# CRSC0002.net
KiCad netlist of a schematic drawn in Altium Designer
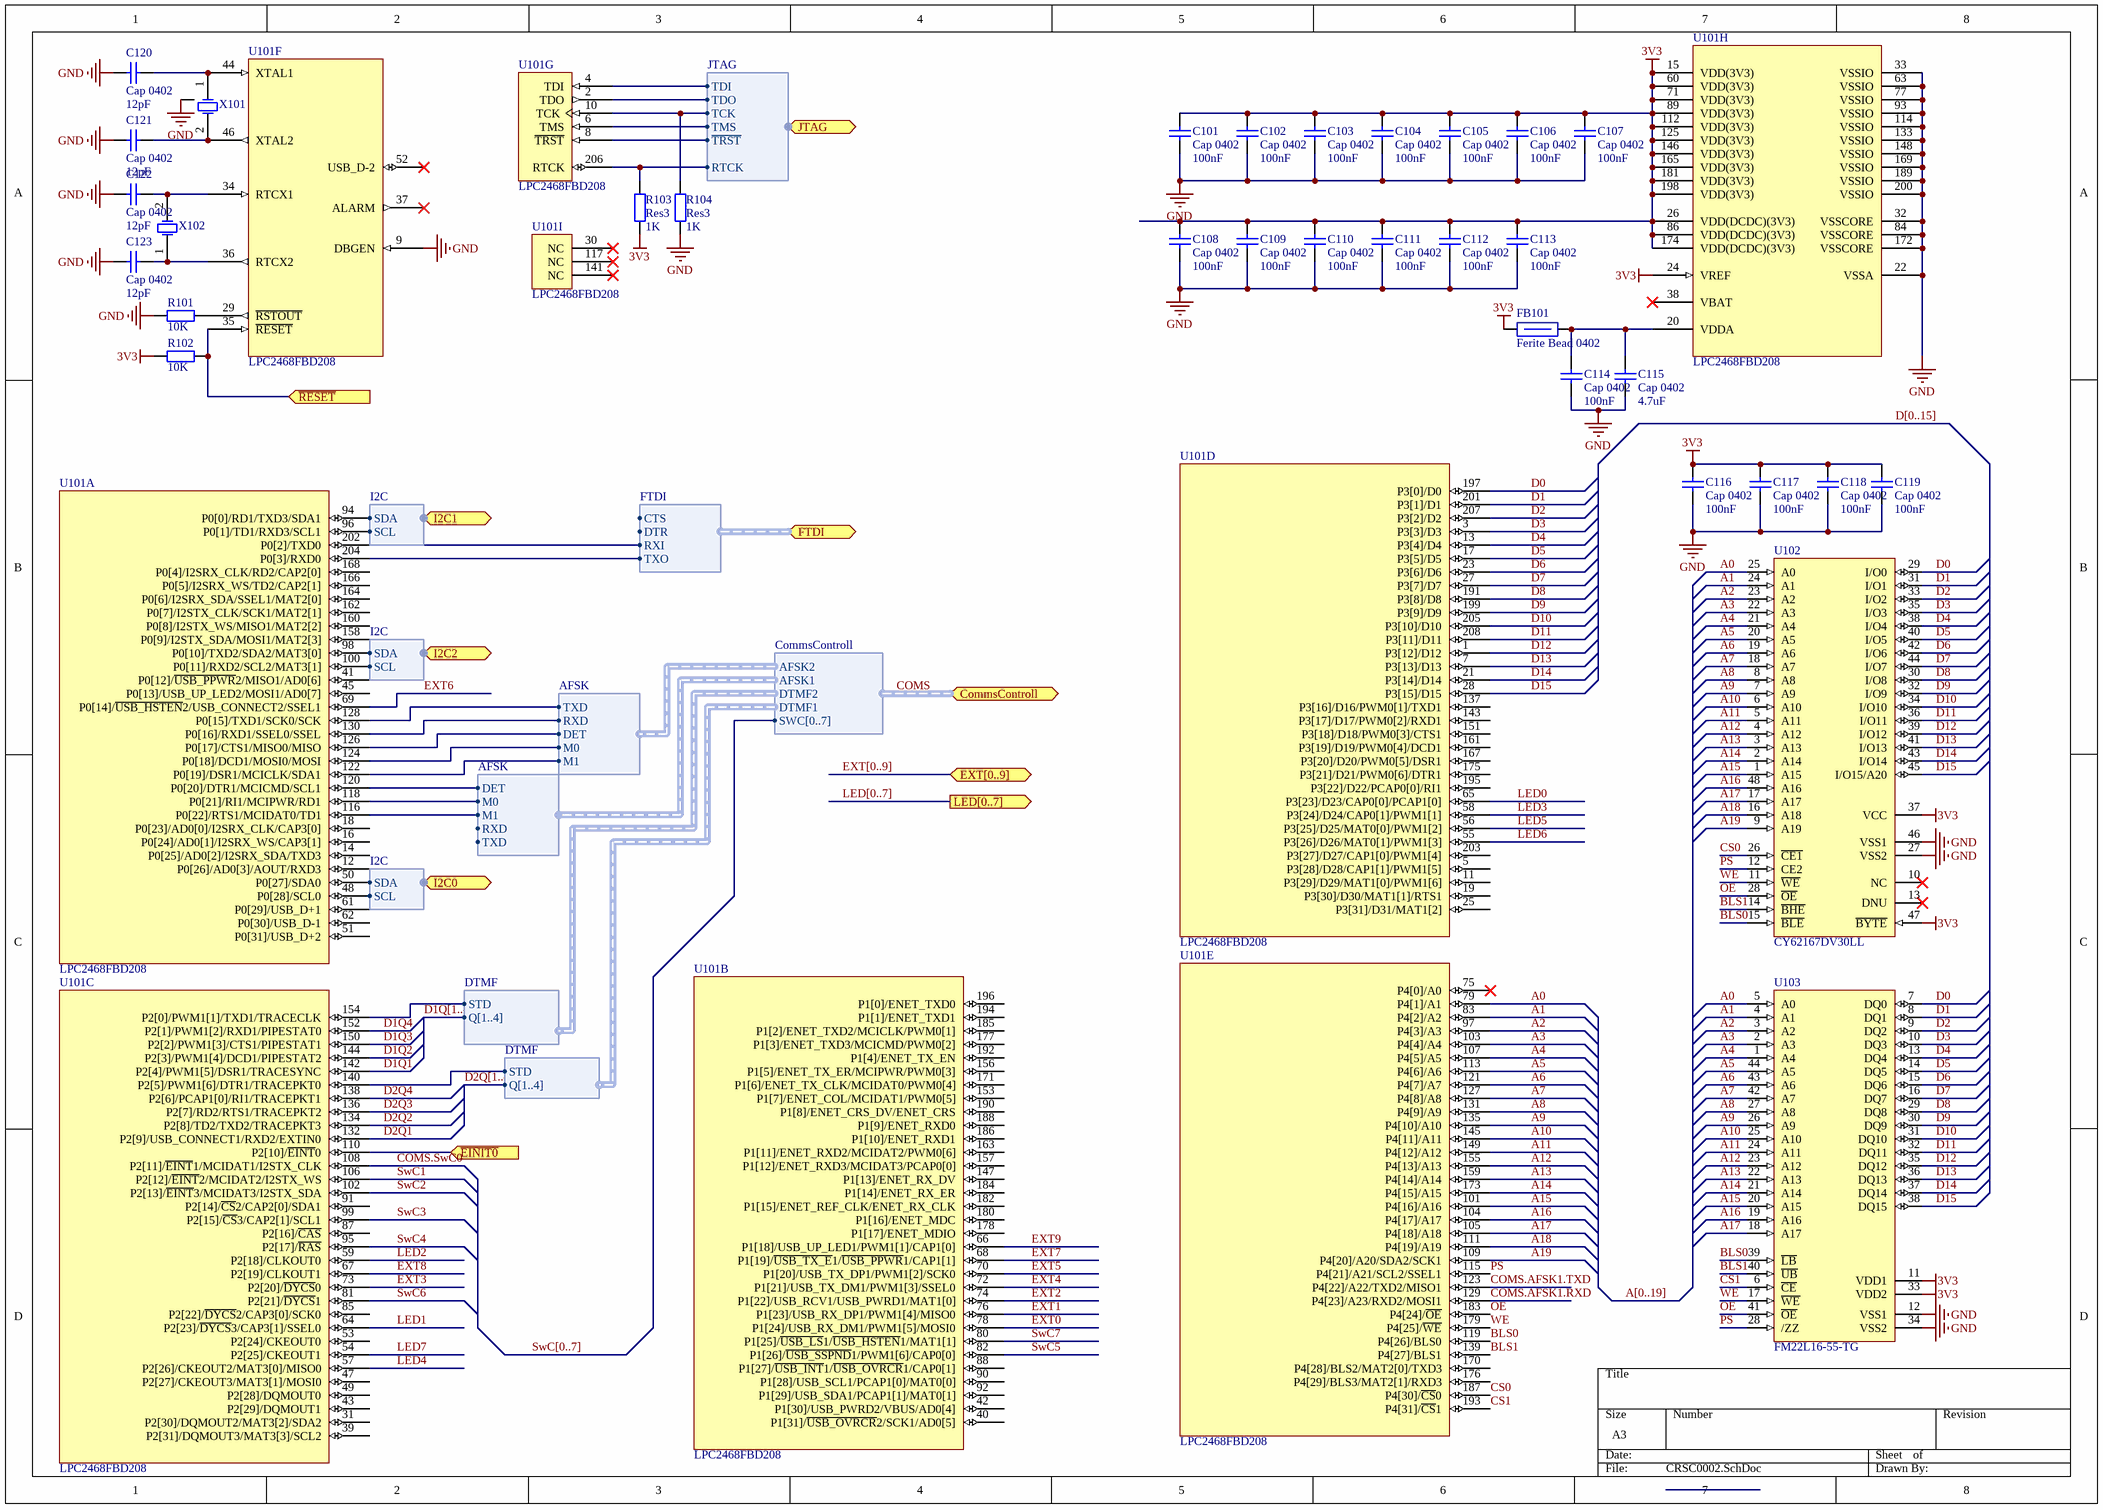
[diagram p0: CRSC0002.SchDoc]

(export (version "E")
  (design (tool "Eeschema 10.0.6"))
  (components
    (comp (ref "C101")
      (value "Cap 0402")
      (footprint "CAPC1005X06L")
      (description "Capacitor")
      (fields (field (name "ALTIUM_VALUE") "100nF") (field (name "PUBLISHER") "Altium Limited"))
      (libsource (lib "CSC") (part "Cap 0402"))
    )
    (comp (ref "C102")
      (value "Cap 0402")
      (footprint "CAPC1005X06L")
      (description "Capacitor")
      (fields (field (name "ALTIUM_VALUE") "100nF") (field (name "PUBLISHER") "Altium Limited"))
      (libsource (lib "CSC") (part "Cap 0402"))
    )
    (comp (ref "C103")
      (value "Cap 0402")
      (footprint "CAPC1005X06L")
      (description "Capacitor")
      (fields (field (name "ALTIUM_VALUE") "100nF") (field (name "PUBLISHER") "Altium Limited"))
      (libsource (lib "CSC") (part "Cap 0402"))
    )
    (comp (ref "C104")
      (value "Cap 0402")
      (footprint "CAPC1005X06L")
      (description "Capacitor")
      (fields (field (name "ALTIUM_VALUE") "100nF") (field (name "PUBLISHER") "Altium Limited"))
      (libsource (lib "CSC") (part "Cap 0402"))
    )
    (comp (ref "C105")
      (value "Cap 0402")
      (footprint "CAPC1005X06L")
      (description "Capacitor")
      (fields (field (name "ALTIUM_VALUE") "100nF") (field (name "PUBLISHER") "Altium Limited"))
      (libsource (lib "CSC") (part "Cap 0402"))
    )
    (comp (ref "C106")
      (value "Cap 0402")
      (footprint "CAPC1005X06L")
      (description "Capacitor")
      (fields (field (name "ALTIUM_VALUE") "100nF") (field (name "PUBLISHER") "Altium Limited"))
      (libsource (lib "CSC") (part "Cap 0402"))
    )
    (comp (ref "C107")
      (value "Cap 0402")
      (footprint "CAPC1005X06L")
      (description "Capacitor")
      (fields (field (name "ALTIUM_VALUE") "100nF") (field (name "PUBLISHER") "Altium Limited"))
      (libsource (lib "CSC") (part "Cap 0402"))
    )
    (comp (ref "C108")
      (value "Cap 0402")
      (footprint "CAPC1005X06L")
      (description "Capacitor")
      (fields (field (name "ALTIUM_VALUE") "100nF") (field (name "PUBLISHER") "Altium Limited"))
      (libsource (lib "CSC") (part "Cap 0402"))
    )
    (comp (ref "C109")
      (value "Cap 0402")
      (footprint "CAPC1005X06L")
      (description "Capacitor")
      (fields (field (name "ALTIUM_VALUE") "100nF") (field (name "PUBLISHER") "Altium Limited"))
      (libsource (lib "CSC") (part "Cap 0402"))
    )
    (comp (ref "C110")
      (value "Cap 0402")
      (footprint "CAPC1005X06L")
      (description "Capacitor")
      (fields (field (name "ALTIUM_VALUE") "100nF") (field (name "PUBLISHER") "Altium Limited"))
      (libsource (lib "CSC") (part "Cap 0402"))
    )
    (comp (ref "C111")
      (value "Cap 0402")
      (footprint "CAPC1005X06L")
      (description "Capacitor")
      (fields (field (name "ALTIUM_VALUE") "100nF") (field (name "PUBLISHER") "Altium Limited"))
      (libsource (lib "CSC") (part "Cap 0402"))
    )
    (comp (ref "C112")
      (value "Cap 0402")
      (footprint "CAPC1005X06L")
      (description "Capacitor")
      (fields (field (name "ALTIUM_VALUE") "100nF") (field (name "PUBLISHER") "Altium Limited"))
      (libsource (lib "CSC") (part "Cap 0402"))
    )
    (comp (ref "C113")
      (value "Cap 0402")
      (footprint "CAPC1005X06L")
      (description "Capacitor")
      (fields (field (name "ALTIUM_VALUE") "100nF") (field (name "PUBLISHER") "Altium Limited"))
      (libsource (lib "CSC") (part "Cap 0402"))
    )
    (comp (ref "C114")
      (value "Cap 0402")
      (footprint "CAPC1005X06L")
      (description "Capacitor")
      (fields (field (name "ALTIUM_VALUE") "100nF") (field (name "PUBLISHER") "Altium Limited"))
      (libsource (lib "CSC") (part "Cap 0402"))
    )
    (comp (ref "C115")
      (value "Cap 0402")
      (footprint "CAPC1005X06L")
      (description "Capacitor")
      (fields (field (name "ALTIUM_VALUE") "4.7uF") (field (name "PUBLISHER") "Altium Limited"))
      (libsource (lib "CSC") (part "Cap 0402"))
    )
    (comp (ref "C116")
      (value "Cap 0402")
      (footprint "CAPC1005X06L")
      (description "Capacitor")
      (fields (field (name "ALTIUM_VALUE") "100nF") (field (name "PUBLISHER") "Altium Limited"))
      (libsource (lib "CSC") (part "Cap 0402"))
    )
    (comp (ref "C117")
      (value "Cap 0402")
      (footprint "CAPC1005X06L")
      (description "Capacitor")
      (fields (field (name "ALTIUM_VALUE") "100nF") (field (name "PUBLISHER") "Altium Limited"))
      (libsource (lib "CSC") (part "Cap 0402"))
    )
    (comp (ref "C118")
      (value "Cap 0402")
      (footprint "CAPC1005X06L")
      (description "Capacitor")
      (fields (field (name "ALTIUM_VALUE") "100nF") (field (name "PUBLISHER") "Altium Limited"))
      (libsource (lib "CSC") (part "Cap 0402"))
    )
    (comp (ref "C119")
      (value "Cap 0402")
      (footprint "CAPC1005X06L")
      (description "Capacitor")
      (fields (field (name "ALTIUM_VALUE") "100nF") (field (name "PUBLISHER") "Altium Limited"))
      (libsource (lib "CSC") (part "Cap 0402"))
    )
    (comp (ref "C120")
      (value "Cap 0402")
      (footprint "CAPC1005X06L")
      (description "Capacitor")
      (fields (field (name "ALTIUM_VALUE") "12pF") (field (name "PUBLISHER") "Altium Limited"))
      (libsource (lib "CSC") (part "Cap 0402"))
    )
    (comp (ref "C121")
      (value "Cap 0402")
      (footprint "CAPC1005X06L")
      (description "Capacitor")
      (fields (field (name "ALTIUM_VALUE") "12pF") (field (name "PUBLISHER") "Altium Limited"))
      (libsource (lib "CSC") (part "Cap 0402"))
    )
    (comp (ref "C122")
      (value "Cap 0402")
      (footprint "CAPC1005X06L")
      (description "Capacitor")
      (fields (field (name "ALTIUM_VALUE") "12pF") (field (name "PUBLISHER") "Altium Limited"))
      (libsource (lib "CSC") (part "Cap 0402"))
    )
    (comp (ref "C123")
      (value "Cap 0402")
      (footprint "CAPC1005X06L")
      (description "Capacitor")
      (fields (field (name "ALTIUM_VALUE") "12pF") (field (name "PUBLISHER") "Altium Limited"))
      (libsource (lib "CSC") (part "Cap 0402"))
    )
    (comp (ref "FB101")
      (value "Ferite Bead 0402")
      (footprint "INDC1005X06L")
      (description "Ferite Bead : 0402")
      (fields (field (name "PUBLISHER") "Altium Limited"))
      (libsource (lib "CSC") (part "FB_0402"))
    )
    (comp (ref "R101")
      (value "10K")
      (footprint "RESC1005X06L")
      (description "Resistor")
      (fields (field (name "Comment") "Res3") (field (name "PUBLISHER") "Altium Limited"))
      (libsource (lib "") (part "Res3_1"))
    )
    (comp (ref "R102")
      (value "10K")
      (footprint "RESC1005X06L")
      (description "Resistor")
      (fields (field (name "Comment") "Res3") (field (name "PUBLISHER") "Altium Limited"))
      (libsource (lib "") (part "Res3_1"))
    )
    (comp (ref "R103")
      (value "Res3")
      (footprint "RESC1005X06L")
      (description "Resistor")
      (fields (field (name "ALTIUM_VALUE") "1K") (field (name "PUBLISHER") "Altium Limited"))
      (libsource (lib "CSC") (part "Res3"))
    )
    (comp (ref "R104")
      (value "Res3")
      (footprint "RESC1005X06L")
      (description "Resistor")
      (fields (field (name "ALTIUM_VALUE") "1K") (field (name "PUBLISHER") "Altium Limited"))
      (libsource (lib "CSC") (part "Res3"))
    )
    (comp (ref "U101")
      (value "LPC2468FBD208")
      (footprint "TSQFP50P3000X3000X160-208L")
      (description "ARM7 16/32-Bit Microcontroller, 512KB Flash, 98KB RAM, 208-Lead LQFP")
      (fields (field (name "PUBLISHER") "Altium Limited"))
      (libsource (lib "CSC") (part "LPC2468FBD208"))
    )
    (comp (ref "U102")
      (value "CY62167DV30LL")
      (footprint "TSSOP50P2000X120-48L")
      (description "16-Mbit (1M x 16) Static RAM")
      (fields (field (name "PUBLISHER") "Altium Limited"))
      (libsource (lib "CSC") (part "CY62167DV30LL"))
    )
    (comp (ref "U103")
      (value "FM22L16-55-TG")
      (footprint "TSOP80P1180X120-44L")
      (description "FRAM, 2MB, 3V, 60NS, 44TSOP2")
      (libsource (lib "CSC") (part "FM22L16-55-TG"))
    )
    (comp (ref "X101")
      (value "Crystal Oscilator")
      (footprint "7M")
      (description "Crystal Oscillator")
      (fields (field (name "PUBLISHER") "Altium Limited"))
      (libsource (lib "CSC") (part "C.O. 4pins"))
    )
    (comp (ref "X102")
      (value "Crystal Oscilator")
      (footprint "9H T10")
      (description "Crystal Oscillator")
      (fields (field (name "PUBLISHER") "Altium Limited"))
      (libsource (lib "CSC") (part "C.O. 2pins"))
    )
  )
  (nets
    (net (code "8") (name "/A0") (class "Default")
      (node (ref "U101") (pin "79") (pinfunction "P4[1]/A1_79") (pintype "bidirectional"))
      (node (ref "U102") (pin "25") (pinfunction "A0_25") (pintype "input"))
      (node (ref "U103") (pin "5") (pinfunction "A0_5") (pintype "input"))
    )
    (net (code "9") (name "/A1") (class "Default")
      (node (ref "U101") (pin "83") (pinfunction "P4[2]/A2_83") (pintype "bidirectional"))
      (node (ref "U102") (pin "24") (pinfunction "A1_24") (pintype "input"))
      (node (ref "U103") (pin "4") (pinfunction "A1_4") (pintype "input"))
    )
    (net (code "10") (name "/A2") (class "Default")
      (node (ref "U101") (pin "97") (pinfunction "P4[3]/A3_97") (pintype "bidirectional"))
      (node (ref "U102") (pin "23") (pinfunction "A2_23") (pintype "input"))
      (node (ref "U103") (pin "3") (pinfunction "A2_3") (pintype "input"))
    )
    (net (code "11") (name "/A3") (class "Default")
      (node (ref "U101") (pin "103") (pinfunction "P4[4]/A4_103") (pintype "bidirectional"))
      (node (ref "U102") (pin "22") (pinfunction "A3_22") (pintype "input"))
      (node (ref "U103") (pin "2") (pinfunction "A3_2") (pintype "input"))
    )
    (net (code "12") (name "/A4") (class "Default")
      (node (ref "U101") (pin "107") (pinfunction "P4[5]/A5_107") (pintype "bidirectional"))
      (node (ref "U102") (pin "21") (pinfunction "A4_21") (pintype "input"))
      (node (ref "U103") (pin "1") (pinfunction "A4_1") (pintype "input"))
    )
    (net (code "13") (name "/A5") (class "Default")
      (node (ref "U101") (pin "113") (pinfunction "P4[6]/A6_113") (pintype "bidirectional"))
      (node (ref "U102") (pin "20") (pinfunction "A5_20") (pintype "input"))
      (node (ref "U103") (pin "44") (pinfunction "A5_44") (pintype "input"))
    )
    (net (code "14") (name "/A6") (class "Default")
      (node (ref "U101") (pin "121") (pinfunction "P4[7]/A7_121") (pintype "bidirectional"))
      (node (ref "U102") (pin "19") (pinfunction "A6_19") (pintype "input"))
      (node (ref "U103") (pin "43") (pinfunction "A6_43") (pintype "input"))
    )
    (net (code "15") (name "/A7") (class "Default")
      (node (ref "U101") (pin "127") (pinfunction "P4[8]/A8_127") (pintype "bidirectional"))
      (node (ref "U102") (pin "18") (pinfunction "A7_18") (pintype "input"))
      (node (ref "U103") (pin "42") (pinfunction "A7_42") (pintype "input"))
    )
    (net (code "16") (name "/A8") (class "Default")
      (node (ref "U101") (pin "131") (pinfunction "P4[9]/A9_131") (pintype "bidirectional"))
      (node (ref "U102") (pin "8") (pinfunction "A8_8") (pintype "input"))
      (node (ref "U103") (pin "27") (pinfunction "A8_27") (pintype "input"))
    )
    (net (code "17") (name "/A9") (class "Default")
      (node (ref "U101") (pin "135") (pinfunction "P4[10]/A10_135") (pintype "bidirectional"))
      (node (ref "U102") (pin "7") (pinfunction "A9_7") (pintype "input"))
      (node (ref "U103") (pin "26") (pinfunction "A9_26") (pintype "input"))
    )
    (net (code "18") (name "/A10") (class "Default")
      (node (ref "U101") (pin "145") (pinfunction "P4[11]/A11_145") (pintype "bidirectional"))
      (node (ref "U102") (pin "6") (pinfunction "A10_6") (pintype "input"))
      (node (ref "U103") (pin "25") (pinfunction "A10_25") (pintype "input"))
    )
    (net (code "19") (name "/A11") (class "Default")
      (node (ref "U101") (pin "149") (pinfunction "P4[12]/A12_149") (pintype "bidirectional"))
      (node (ref "U102") (pin "5") (pinfunction "A11_5") (pintype "input"))
      (node (ref "U103") (pin "24") (pinfunction "A11_24") (pintype "input"))
    )
    (net (code "20") (name "/A12") (class "Default")
      (node (ref "U101") (pin "155") (pinfunction "P4[13]/A13_155") (pintype "bidirectional"))
      (node (ref "U102") (pin "4") (pinfunction "A12_4") (pintype "input"))
      (node (ref "U103") (pin "23") (pinfunction "A12_23") (pintype "input"))
    )
    (net (code "21") (name "/A13") (class "Default")
      (node (ref "U101") (pin "159") (pinfunction "P4[14]/A14_159") (pintype "bidirectional"))
      (node (ref "U102") (pin "3") (pinfunction "A13_3") (pintype "input"))
      (node (ref "U103") (pin "22") (pinfunction "A13_22") (pintype "input"))
    )
    (net (code "22") (name "/A14") (class "Default")
      (node (ref "U101") (pin "173") (pinfunction "P4[15]/A15_173") (pintype "bidirectional"))
      (node (ref "U102") (pin "2") (pinfunction "A14_2") (pintype "input"))
      (node (ref "U103") (pin "21") (pinfunction "A14_21") (pintype "input"))
    )
    (net (code "23") (name "/A15") (class "Default")
      (node (ref "U101") (pin "101") (pinfunction "P4[16]/A16_101") (pintype "bidirectional"))
      (node (ref "U102") (pin "1") (pinfunction "A15_1") (pintype "input"))
      (node (ref "U103") (pin "20") (pinfunction "A15_20") (pintype "input"))
    )
    (net (code "24") (name "/A16") (class "Default")
      (node (ref "U101") (pin "104") (pinfunction "P4[17]/A17_104") (pintype "bidirectional"))
      (node (ref "U102") (pin "48") (pinfunction "A16_48") (pintype "input"))
      (node (ref "U103") (pin "19") (pinfunction "A16_19") (pintype "input"))
    )
    (net (code "25") (name "/A17") (class "Default")
      (node (ref "U101") (pin "105") (pinfunction "P4[18]/A18_105") (pintype "bidirectional"))
      (node (ref "U102") (pin "17") (pinfunction "A17_17") (pintype "input"))
      (node (ref "U103") (pin "18") (pinfunction "A17_18") (pintype "input"))
    )
    (net (code "26") (name "/A18") (class "Default")
      (node (ref "U101") (pin "111") (pinfunction "P4[19]/A19_111") (pintype "bidirectional"))
      (node (ref "U102") (pin "16") (pinfunction "A18_16") (pintype "input"))
    )
    (net (code "27") (name "/A19") (class "Default")
      (node (ref "U101") (pin "109") (pinfunction "P4[20]/A20/SDA2/SCK1_109") (pintype "bidirectional"))
      (node (ref "U102") (pin "9") (pinfunction "A19_9") (pintype "input"))
    )
    (net (code "29") (name "/BLS0") (class "Default")
      (node (ref "U101") (pin "119") (pinfunction "P4[26]/BLS0_119") (pintype "bidirectional"))
      (node (ref "U102") (pin "15") (pinfunction "~{BLE}_15") (pintype "input"))
      (node (ref "U103") (pin "39") (pinfunction "~{LB}_39") (pintype "input"))
    )
    (net (code "30") (name "/BLS1") (class "Default")
      (node (ref "U101") (pin "139") (pinfunction "P4[27]/BLS1_139") (pintype "bidirectional"))
      (node (ref "U102") (pin "14") (pinfunction "~{BHE}_14") (pintype "input"))
      (node (ref "U103") (pin "40") (pinfunction "~{UB}_40") (pintype "input"))
    )
    (net (code "31") (name "/COMS.AFSK1.RXD") (class "Default")
      (node (ref "U101") (pin "129") (pinfunction "P4[23]/A23/RXD2/MOSI1_129") (pintype "bidirectional"))
    )
    (net (code "32") (name "/COMS.AFSK1.TXD") (class "Default")
      (node (ref "U101") (pin "123") (pinfunction "P4[22]/A22/TXD2/MISO1_123") (pintype "bidirectional"))
    )
    (net (code "33") (name "/COMS.SwC0") (class "Default")
      (node (ref "U101") (pin "108") (pinfunction "P2[11]/~{EINT}1/MCIDAT1/I2STX_CLK_108") (pintype "bidirectional"))
    )
    (net (code "34") (name "/CS0") (class "Default")
      (node (ref "U101") (pin "187") (pinfunction "P4[30]/~{CS}0_187") (pintype "bidirectional"))
      (node (ref "U102") (pin "26") (pinfunction "~{CE1}_26") (pintype "input"))
    )
    (net (code "35") (name "/CS1") (class "Default")
      (node (ref "U101") (pin "193") (pinfunction "P4[31]/~{CS}1_193") (pintype "bidirectional"))
      (node (ref "U103") (pin "6") (pinfunction "~{CE}_6") (pintype "input"))
    )
    (net (code "36") (name "/D0") (class "Default")
      (node (ref "U101") (pin "197") (pinfunction "P3[0]/D0_197") (pintype "bidirectional"))
      (node (ref "U102") (pin "29") (pinfunction "I/O0_29") (pintype "bidirectional"))
      (node (ref "U103") (pin "7") (pinfunction "DQ0_7") (pintype "bidirectional"))
    )
    (net (code "37") (name "/D1") (class "Default")
      (node (ref "U101") (pin "201") (pinfunction "P3[1]/D1_201") (pintype "bidirectional"))
      (node (ref "U102") (pin "31") (pinfunction "I/O1_31") (pintype "bidirectional"))
      (node (ref "U103") (pin "8") (pinfunction "DQ1_8") (pintype "bidirectional"))
    )
    (net (code "38") (name "/D1Q1") (class "Default")
      (node (ref "U101") (pin "142") (pinfunction "P2[4]/PWM1[5]/DSR1/TRACESYNC_142") (pintype "bidirectional"))
    )
    (net (code "39") (name "/D1Q2") (class "Default")
      (node (ref "U101") (pin "144") (pinfunction "P2[3]/PWM1[4]/DCD1/PIPESTAT2_144") (pintype "bidirectional"))
    )
    (net (code "40") (name "/D1Q3") (class "Default")
      (node (ref "U101") (pin "150") (pinfunction "P2[2]/PWM1[3]/CTS1/PIPESTAT1_150") (pintype "bidirectional"))
    )
    (net (code "41") (name "/D1Q4") (class "Default")
      (node (ref "U101") (pin "152") (pinfunction "P2[1]/PWM1[2]/RXD1/PIPESTAT0_152") (pintype "bidirectional"))
    )
    (net (code "42") (name "/D2") (class "Default")
      (node (ref "U101") (pin "207") (pinfunction "P3[2]/D2_207") (pintype "bidirectional"))
      (node (ref "U102") (pin "33") (pinfunction "I/O2_33") (pintype "bidirectional"))
      (node (ref "U103") (pin "9") (pinfunction "DQ2_9") (pintype "bidirectional"))
    )
    (net (code "43") (name "/D2Q1") (class "Default")
      (node (ref "U101") (pin "132") (pinfunction "P2[9]/USB_CONNECT1/RXD2/EXTIN0_132") (pintype "bidirectional"))
    )
    (net (code "44") (name "/D2Q2") (class "Default")
      (node (ref "U101") (pin "134") (pinfunction "P2[8]/TD2/TXD2/TRACEPKT3_134") (pintype "bidirectional"))
    )
    (net (code "45") (name "/D2Q3") (class "Default")
      (node (ref "U101") (pin "136") (pinfunction "P2[7]/RD2/RTS1/TRACEPKT2_136") (pintype "bidirectional"))
    )
    (net (code "46") (name "/D2Q4") (class "Default")
      (node (ref "U101") (pin "138") (pinfunction "P2[6]/PCAP1[0]/RI1/TRACEPKT1_138") (pintype "bidirectional"))
    )
    (net (code "47") (name "/D3") (class "Default")
      (node (ref "U101") (pin "3") (pinfunction "P3[3]/D3_3") (pintype "bidirectional"))
      (node (ref "U102") (pin "35") (pinfunction "I/O3_35") (pintype "bidirectional"))
      (node (ref "U103") (pin "10") (pinfunction "DQ3_10") (pintype "bidirectional"))
    )
    (net (code "48") (name "/D4") (class "Default")
      (node (ref "U101") (pin "13") (pinfunction "P3[4]/D4_13") (pintype "bidirectional"))
      (node (ref "U102") (pin "38") (pinfunction "I/O4_38") (pintype "bidirectional"))
      (node (ref "U103") (pin "13") (pinfunction "DQ4_13") (pintype "bidirectional"))
    )
    (net (code "49") (name "/D5") (class "Default")
      (node (ref "U101") (pin "17") (pinfunction "P3[5]/D5_17") (pintype "bidirectional"))
      (node (ref "U102") (pin "40") (pinfunction "I/O5_40") (pintype "bidirectional"))
      (node (ref "U103") (pin "14") (pinfunction "DQ5_14") (pintype "bidirectional"))
    )
    (net (code "50") (name "/D6") (class "Default")
      (node (ref "U101") (pin "23") (pinfunction "P3[6]/D6_23") (pintype "bidirectional"))
      (node (ref "U102") (pin "42") (pinfunction "I/O6_42") (pintype "bidirectional"))
      (node (ref "U103") (pin "15") (pinfunction "DQ6_15") (pintype "bidirectional"))
    )
    (net (code "51") (name "/D7") (class "Default")
      (node (ref "U101") (pin "27") (pinfunction "P3[7]/D7_27") (pintype "bidirectional"))
      (node (ref "U102") (pin "44") (pinfunction "I/O7_44") (pintype "bidirectional"))
      (node (ref "U103") (pin "16") (pinfunction "DQ7_16") (pintype "bidirectional"))
    )
    (net (code "52") (name "/D8") (class "Default")
      (node (ref "U101") (pin "191") (pinfunction "P3[8]/D8_191") (pintype "bidirectional"))
      (node (ref "U102") (pin "30") (pinfunction "I/O8_30") (pintype "bidirectional"))
      (node (ref "U103") (pin "29") (pinfunction "DQ8_29") (pintype "bidirectional"))
    )
    (net (code "53") (name "/D9") (class "Default")
      (node (ref "U101") (pin "199") (pinfunction "P3[9]/D9_199") (pintype "bidirectional"))
      (node (ref "U102") (pin "32") (pinfunction "I/O9_32") (pintype "bidirectional"))
      (node (ref "U103") (pin "30") (pinfunction "DQ9_30") (pintype "bidirectional"))
    )
    (net (code "54") (name "/D10") (class "Default")
      (node (ref "U101") (pin "205") (pinfunction "P3[10]/D10_205") (pintype "bidirectional"))
      (node (ref "U102") (pin "34") (pinfunction "I/O10_34") (pintype "bidirectional"))
      (node (ref "U103") (pin "31") (pinfunction "DQ10_31") (pintype "bidirectional"))
    )
    (net (code "55") (name "/D11") (class "Default")
      (node (ref "U101") (pin "208") (pinfunction "P3[11]/D11_208") (pintype "bidirectional"))
      (node (ref "U102") (pin "36") (pinfunction "I/O11_36") (pintype "bidirectional"))
      (node (ref "U103") (pin "32") (pinfunction "DQ11_32") (pintype "bidirectional"))
    )
    (net (code "56") (name "/D12") (class "Default")
      (node (ref "U101") (pin "1") (pinfunction "P3[12]/D12_1") (pintype "bidirectional"))
      (node (ref "U102") (pin "39") (pinfunction "I/O12_39") (pintype "bidirectional"))
      (node (ref "U103") (pin "35") (pinfunction "DQ12_35") (pintype "bidirectional"))
    )
    (net (code "57") (name "/D13") (class "Default")
      (node (ref "U101") (pin "7") (pinfunction "P3[13]/D13_7") (pintype "bidirectional"))
      (node (ref "U102") (pin "41") (pinfunction "I/O13_41") (pintype "bidirectional"))
      (node (ref "U103") (pin "36") (pinfunction "DQ13_36") (pintype "bidirectional"))
    )
    (net (code "58") (name "/D14") (class "Default")
      (node (ref "U101") (pin "21") (pinfunction "P3[14]/D14_21") (pintype "bidirectional"))
      (node (ref "U102") (pin "43") (pinfunction "I/O14_43") (pintype "bidirectional"))
      (node (ref "U103") (pin "37") (pinfunction "DQ14_37") (pintype "bidirectional"))
    )
    (net (code "59") (name "/D15") (class "Default")
      (node (ref "U101") (pin "28") (pinfunction "P3[15]/D15_28") (pintype "bidirectional"))
      (node (ref "U102") (pin "45") (pinfunction "I/O15/A20_45") (pintype "bidirectional"))
      (node (ref "U103") (pin "38") (pinfunction "DQ15_38") (pintype "bidirectional"))
    )
    (net (code "61") (name "/EXT0") (class "Default")
      (node (ref "U101") (pin "78") (pinfunction "P1[24]/USB_RX_DM1/PWM1[5]/MOSI0_78") (pintype "bidirectional"))
    )
    (net (code "62") (name "/EXT1") (class "Default")
      (node (ref "U101") (pin "76") (pinfunction "P1[23]/USB_RX_DP1/PWM1[4]/MISO0_76") (pintype "bidirectional"))
    )
    (net (code "63") (name "/EXT2") (class "Default")
      (node (ref "U101") (pin "74") (pinfunction "P1[22]/USB_RCV1/USB_PWRD1/MAT1[0]_74") (pintype "bidirectional"))
    )
    (net (code "64") (name "/EXT3") (class "Default")
      (node (ref "U101") (pin "73") (pinfunction "P2[20]/~{DYCS}0_73") (pintype "bidirectional"))
    )
    (net (code "65") (name "/EXT4") (class "Default")
      (node (ref "U101") (pin "72") (pinfunction "P1[21]/USB_TX_DM1/PWM1[3]/SSEL0_72") (pintype "bidirectional"))
    )
    (net (code "66") (name "/EXT5") (class "Default")
      (node (ref "U101") (pin "70") (pinfunction "P1[20]/USB_TX_DP1/PWM1[2]/SCK0_70") (pintype "bidirectional"))
    )
    (net (code "67") (name "/EXT6") (class "Default")
      (node (ref "U101") (pin "69") (pinfunction "P0[14]/~{USB_HSTEN}2/USB_CONNECT2/SSEL1_69") (pintype "bidirectional"))
    )
    (net (code "68") (name "/EXT7") (class "Default")
      (node (ref "U101") (pin "68") (pinfunction "P1[19]/~{USB_TX_E}1/~{USB_PPWR}1/CAP1[1]_68") (pintype "bidirectional"))
    )
    (net (code "69") (name "/EXT8") (class "Default")
      (node (ref "U101") (pin "67") (pinfunction "P2[19]/CLKOUT1_67") (pintype "bidirectional"))
    )
    (net (code "70") (name "/EXT9") (class "Default")
      (node (ref "U101") (pin "66") (pinfunction "P1[18]/USB_UP_LED1/PWM1[1]/CAP1[0]_66") (pintype "bidirectional"))
    )
    (net (code "72") (name "/LED0") (class "Default")
      (node (ref "U101") (pin "65") (pinfunction "P3[23]/D23/CAP0[0]/PCAP1[0]_65") (pintype "bidirectional"))
    )
    (net (code "73") (name "/LED1") (class "Default")
      (node (ref "U101") (pin "64") (pinfunction "P2[23]/~{DYCS}3/CAP3[1]/SSEL0_64") (pintype "bidirectional"))
    )
    (net (code "74") (name "/LED2") (class "Default")
      (node (ref "U101") (pin "59") (pinfunction "P2[18]/CLKOUT0_59") (pintype "bidirectional"))
    )
    (net (code "75") (name "/LED3") (class "Default")
      (node (ref "U101") (pin "58") (pinfunction "P3[24]/D24/CAP0[1]/PWM1[1]_58") (pintype "bidirectional"))
    )
    (net (code "76") (name "/LED4") (class "Default")
      (node (ref "U101") (pin "57") (pinfunction "P2[26]/CKEOUT2/MAT3[0]/MISO0_57") (pintype "bidirectional"))
    )
    (net (code "77") (name "/LED5") (class "Default")
      (node (ref "U101") (pin "56") (pinfunction "P3[25]/D25/MAT0[0]/PWM1[2]_56") (pintype "bidirectional"))
    )
    (net (code "78") (name "/LED6") (class "Default")
      (node (ref "U101") (pin "55") (pinfunction "P3[26]/D26/MAT0[1]/PWM1[3]_55") (pintype "bidirectional"))
    )
    (net (code "79") (name "/LED7") (class "Default")
      (node (ref "U101") (pin "54") (pinfunction "P2[25]/CKEOUT1_54") (pintype "bidirectional"))
    )
    (net (code "81") (name "/OE") (class "Default")
      (node (ref "U101") (pin "183") (pinfunction "P4[24]/~{OE}_183") (pintype "bidirectional"))
      (node (ref "U102") (pin "28") (pinfunction "~{OE}_28") (pintype "input"))
      (node (ref "U103") (pin "41") (pinfunction "~{OE}_41") (pintype "input"))
    )
    (net (code "82") (name "/PS") (class "Default")
      (node (ref "U101") (pin "115") (pinfunction "P4[21]/A21/SCL2/SSEL1_115") (pintype "bidirectional"))
      (node (ref "U102") (pin "12") (pinfunction "CE2_12") (pintype "input"))
      (node (ref "U103") (pin "28") (pinfunction "/ZZ_28") (pintype "input"))
    )
    (net (code "83") (name "/RTCK") (class "Default")
      (node (ref "R103") (pin "1") (pinfunction "1_1") (pintype "passive"))
      (node (ref "U101") (pin "206") (pinfunction "RTCK_206") (pintype "bidirectional"))
    )
    (net (code "84") (name "/RXI") (class "Default")
      (node (ref "U101") (pin "202") (pinfunction "P0[2]/TXD0_202") (pintype "bidirectional"))
    )
    (net (code "85") (name "/SwC1") (class "Default")
      (node (ref "U101") (pin "106") (pinfunction "P2[12]/~{EINT}2/MCIDAT2/I2STX_WS_106") (pintype "bidirectional"))
    )
    (net (code "86") (name "/SwC2") (class "Default")
      (node (ref "U101") (pin "102") (pinfunction "P2[13]/~{EINT}3/MCIDAT3/I2STX_SDA_102") (pintype "bidirectional"))
    )
    (net (code "87") (name "/SwC3") (class "Default")
      (node (ref "U101") (pin "99") (pinfunction "P2[15]/~{CS}3/CAP2[1]/SCL1_99") (pintype "bidirectional"))
    )
    (net (code "88") (name "/SwC4") (class "Default")
      (node (ref "U101") (pin "95") (pinfunction "P2[17]/~{RAS}_95") (pintype "bidirectional"))
    )
    (net (code "89") (name "/SwC5") (class "Default")
      (node (ref "U101") (pin "82") (pinfunction "P1[26]/~{USB_SSPND}1/PWM1[6]/CAP0[0]_82") (pintype "bidirectional"))
    )
    (net (code "90") (name "/SwC6") (class "Default")
      (node (ref "U101") (pin "81") (pinfunction "P2[21]/~{DYCS}1_81") (pintype "bidirectional"))
    )
    (net (code "91") (name "/SwC7") (class "Default")
      (node (ref "U101") (pin "80") (pinfunction "P1[25]/~{USB_LS}1/~{USB_HSTEN}1/MAT1[1]_80") (pintype "bidirectional"))
    )
    (net (code "93") (name "/TCK") (class "Default")
      (node (ref "R104") (pin "1") (pinfunction "1_1") (pintype "passive"))
      (node (ref "U101") (pin "10") (pinfunction "TCK_10") (pintype "input"))
    )
    (net (code "94") (name "/TDI") (class "Default")
      (node (ref "U101") (pin "4") (pinfunction "TDI_4") (pintype "input"))
    )
    (net (code "95") (name "/TDO") (class "Default")
      (node (ref "U101") (pin "2") (pinfunction "TDO_2") (pintype "output"))
    )
    (net (code "96") (name "/TMS") (class "Default")
      (node (ref "U101") (pin "6") (pinfunction "TMS_6") (pintype "input"))
    )
    (net (code "97") (name "/TXO") (class "Default")
      (node (ref "U101") (pin "204") (pinfunction "P0[3]/RXD0_204") (pintype "bidirectional"))
    )
    (net (code "98") (name "/WE") (class "Default")
      (node (ref "U101") (pin "179") (pinfunction "P4[25]/~{WE}_179") (pintype "bidirectional"))
      (node (ref "U102") (pin "11") (pinfunction "~{WE}_11") (pintype "input"))
      (node (ref "U103") (pin "17") (pinfunction "~{WE}_17") (pintype "input"))
    )
    (net (code "107") (name "/~{EINIT0}") (class "Default")
      (node (ref "U101") (pin "110") (pinfunction "P2[10]/~{EINT}0_110") (pintype "bidirectional"))
    )
    (net (code "108") (name "/~{RESET}") (class "Default")
      (node (ref "R102") (pin "1") (pinfunction "1_1") (pintype "passive"))
      (node (ref "U101") (pin "35") (pinfunction "~{RESET}_35") (pintype "input"))
    )
    (net (code "109") (name "/~{TRST}") (class "Default")
      (node (ref "U101") (pin "8") (pinfunction "~{TRST}_8") (pintype "input"))
    )
    (net (code "110") (name "3V3") (class "Default")
      (node (ref "C101") (pin "2") (pinfunction "2_2") (pintype "passive"))
      (node (ref "C102") (pin "2") (pinfunction "2_2") (pintype "passive"))
      (node (ref "C103") (pin "2") (pinfunction "2_2") (pintype "passive"))
      (node (ref "C104") (pin "2") (pinfunction "2_2") (pintype "passive"))
      (node (ref "C105") (pin "2") (pinfunction "2_2") (pintype "passive"))
      (node (ref "C106") (pin "2") (pinfunction "2_2") (pintype "passive"))
      (node (ref "C107") (pin "2") (pinfunction "2_2") (pintype "passive"))
      (node (ref "C108") (pin "2") (pinfunction "2_2") (pintype "passive"))
      (node (ref "C109") (pin "2") (pinfunction "2_2") (pintype "passive"))
      (node (ref "C110") (pin "2") (pinfunction "2_2") (pintype "passive"))
      (node (ref "C111") (pin "2") (pinfunction "2_2") (pintype "passive"))
      (node (ref "C112") (pin "2") (pinfunction "2_2") (pintype "passive"))
      (node (ref "C113") (pin "2") (pinfunction "2_2") (pintype "passive"))
      (node (ref "C116") (pin "2") (pinfunction "2_2") (pintype "passive"))
      (node (ref "C117") (pin "2") (pinfunction "2_2") (pintype "passive"))
      (node (ref "C118") (pin "2") (pinfunction "2_2") (pintype "passive"))
      (node (ref "C119") (pin "2") (pinfunction "2_2") (pintype "passive"))
      (node (ref "FB101") (pin "1") (pinfunction "1_1") (pintype "passive"))
      (node (ref "R102") (pin "2") (pinfunction "2_2") (pintype "passive"))
      (node (ref "R103") (pin "2") (pinfunction "2_2") (pintype "passive"))
      (node (ref "U101") (pin "112") (pinfunction "VDD(3V3)_112") (pintype "power_in"))
      (node (ref "U101") (pin "125") (pinfunction "VDD(3V3)_125") (pintype "power_in"))
      (node (ref "U101") (pin "146") (pinfunction "VDD(3V3)_146") (pintype "power_in"))
      (node (ref "U101") (pin "15") (pinfunction "VDD(3V3)_15") (pintype "power_in"))
      (node (ref "U101") (pin "165") (pinfunction "VDD(3V3)_165") (pintype "power_in"))
      (node (ref "U101") (pin "174") (pinfunction "VDD(DCDC)(3V3)_174") (pintype "power_in"))
      (node (ref "U101") (pin "181") (pinfunction "VDD(3V3)_181") (pintype "power_in"))
      (node (ref "U101") (pin "198") (pinfunction "VDD(3V3)_198") (pintype "power_in"))
      (node (ref "U101") (pin "24") (pinfunction "VREF_24") (pintype "input"))
      (node (ref "U101") (pin "26") (pinfunction "VDD(DCDC)(3V3)_26") (pintype "power_in"))
      (node (ref "U101") (pin "60") (pinfunction "VDD(3V3)_60") (pintype "power_in"))
      (node (ref "U101") (pin "71") (pinfunction "VDD(3V3)_71") (pintype "power_in"))
      (node (ref "U101") (pin "86") (pinfunction "VDD(DCDC)(3V3)_86") (pintype "power_in"))
      (node (ref "U101") (pin "89") (pinfunction "VDD(3V3)_89") (pintype "power_in"))
      (node (ref "U102") (pin "37") (pinfunction "VCC_37") (pintype "power_in"))
      (node (ref "U102") (pin "47") (pinfunction "~{BYTE}_47") (pintype "input"))
      (node (ref "U103") (pin "11") (pinfunction "VDD1_11") (pintype "power_in"))
      (node (ref "U103") (pin "33") (pinfunction "VDD2_33") (pintype "power_in"))
    )
    (net (code "111") (name "GND") (class "Default")
      (node (ref "C101") (pin "1") (pinfunction "1_1") (pintype "passive"))
      (node (ref "C102") (pin "1") (pinfunction "1_1") (pintype "passive"))
      (node (ref "C103") (pin "1") (pinfunction "1_1") (pintype "passive"))
      (node (ref "C104") (pin "1") (pinfunction "1_1") (pintype "passive"))
      (node (ref "C105") (pin "1") (pinfunction "1_1") (pintype "passive"))
      (node (ref "C106") (pin "1") (pinfunction "1_1") (pintype "passive"))
      (node (ref "C107") (pin "1") (pinfunction "1_1") (pintype "passive"))
      (node (ref "C108") (pin "1") (pinfunction "1_1") (pintype "passive"))
      (node (ref "C109") (pin "1") (pinfunction "1_1") (pintype "passive"))
      (node (ref "C110") (pin "1") (pinfunction "1_1") (pintype "passive"))
      (node (ref "C111") (pin "1") (pinfunction "1_1") (pintype "passive"))
      (node (ref "C112") (pin "1") (pinfunction "1_1") (pintype "passive"))
      (node (ref "C113") (pin "1") (pinfunction "1_1") (pintype "passive"))
      (node (ref "C114") (pin "1") (pinfunction "1_1") (pintype "passive"))
      (node (ref "C115") (pin "1") (pinfunction "1_1") (pintype "passive"))
      (node (ref "C116") (pin "1") (pinfunction "1_1") (pintype "passive"))
      (node (ref "C117") (pin "1") (pinfunction "1_1") (pintype "passive"))
      (node (ref "C118") (pin "1") (pinfunction "1_1") (pintype "passive"))
      (node (ref "C119") (pin "1") (pinfunction "1_1") (pintype "passive"))
      (node (ref "C120") (pin "2") (pinfunction "2_2") (pintype "passive"))
      (node (ref "C121") (pin "1") (pinfunction "1_1") (pintype "passive"))
      (node (ref "C122") (pin "2") (pinfunction "2_2") (pintype "passive"))
      (node (ref "C123") (pin "1") (pinfunction "1_1") (pintype "passive"))
      (node (ref "R101") (pin "2") (pinfunction "2_2") (pintype "passive"))
      (node (ref "R104") (pin "2") (pinfunction "2_2") (pintype "passive"))
      (node (ref "U101") (pin "114") (pinfunction "VSSIO_114") (pintype "power_in"))
      (node (ref "U101") (pin "133") (pinfunction "VSSIO_133") (pintype "power_in"))
      (node (ref "U101") (pin "148") (pinfunction "VSSIO_148") (pintype "power_in"))
      (node (ref "U101") (pin "169") (pinfunction "VSSIO_169") (pintype "power_in"))
      (node (ref "U101") (pin "172") (pinfunction "VSSCORE_172") (pintype "power_in"))
      (node (ref "U101") (pin "189") (pinfunction "VSSIO_189") (pintype "power_in"))
      (node (ref "U101") (pin "200") (pinfunction "VSSIO_200") (pintype "power_in"))
      (node (ref "U101") (pin "22") (pinfunction "VSSA_22") (pintype "power_in"))
      (node (ref "U101") (pin "32") (pinfunction "VSSCORE_32") (pintype "power_in"))
      (node (ref "U101") (pin "33") (pinfunction "VSSIO_33") (pintype "power_in"))
      (node (ref "U101") (pin "63") (pinfunction "VSSIO_63") (pintype "power_in"))
      (node (ref "U101") (pin "77") (pinfunction "VSSIO_77") (pintype "power_in"))
      (node (ref "U101") (pin "84") (pinfunction "VSSCORE_84") (pintype "power_in"))
      (node (ref "U101") (pin "9") (pinfunction "DBGEN_9") (pintype "input"))
      (node (ref "U101") (pin "93") (pinfunction "VSSIO_93") (pintype "power_in"))
      (node (ref "U102") (pin "27") (pinfunction "VSS2_27") (pintype "power_in"))
      (node (ref "U102") (pin "46") (pinfunction "VSS1_46") (pintype "power_in"))
      (node (ref "U103") (pin "12") (pinfunction "VSS1_12") (pintype "power_in"))
      (node (ref "U103") (pin "34") (pinfunction "VSS2_34") (pintype "power_in"))
      (node (ref "X101") (pin "3") (pinfunction "3_3") (pintype "passive"))
    )
    (net (code "112") (name "Net-(U101F-RTCX1)") (class "Default")
      (node (ref "C122") (pin "1") (pinfunction "1_1") (pintype "passive"))
      (node (ref "U101") (pin "34") (pinfunction "RTCX1_34") (pintype "input"))
      (node (ref "X102") (pin "2") (pinfunction "OSC2_2") (pintype "passive"))
    )
    (net (code "113") (name "Net-(U101F-RTCX2)") (class "Default")
      (node (ref "C123") (pin "2") (pinfunction "2_2") (pintype "passive"))
      (node (ref "U101") (pin "36") (pinfunction "RTCX2_36") (pintype "output"))
      (node (ref "X102") (pin "1") (pinfunction "OSC1_1") (pintype "passive"))
    )
    (net (code "114") (name "Net-(U101F-XTAL1)") (class "Default")
      (node (ref "C120") (pin "1") (pinfunction "1_1") (pintype "passive"))
      (node (ref "U101") (pin "44") (pinfunction "XTAL1_44") (pintype "input"))
      (node (ref "X101") (pin "1") (pinfunction "OSC1_1") (pintype "passive"))
    )
    (net (code "115") (name "Net-(U101F-XTAL2)") (class "Default")
      (node (ref "C121") (pin "2") (pinfunction "2_2") (pintype "passive"))
      (node (ref "U101") (pin "46") (pinfunction "XTAL2_46") (pintype "output"))
      (node (ref "X101") (pin "2") (pinfunction "OSC2_2") (pintype "passive"))
    )
    (net (code "116") (name "Net-(U101F-~{RSTOUT})") (class "Default")
      (node (ref "R101") (pin "1") (pinfunction "1_1") (pintype "passive"))
      (node (ref "U101") (pin "29") (pinfunction "~{RSTOUT}_29") (pintype "output"))
    )
    (net (code "117") (name "Net-(U101H-VDDA)") (class "Default")
      (node (ref "C114") (pin "2") (pinfunction "2_2") (pintype "passive"))
      (node (ref "C115") (pin "2") (pinfunction "2_2") (pintype "passive"))
      (node (ref "FB101") (pin "2") (pinfunction "2_2") (pintype "passive"))
      (node (ref "U101") (pin "20") (pinfunction "VDDA_20") (pintype "power_in"))
    )
    (net (code "118") (name "unconnected-(U101A-P0[0]{slash}RD1{slash}TXD3{slash}SDA1-Pad94)") (class "Default")
      (node (ref "U101") (pin "94") (pinfunction "P0[0]/RD1/TXD3/SDA1_94") (pintype "bidirectional"))
    )
    (net (code "119") (name "unconnected-(U101A-P0[1]{slash}TD1{slash}RXD3{slash}SCL1-Pad96)") (class "Default")
      (node (ref "U101") (pin "96") (pinfunction "P0[1]/TD1/RXD3/SCL1_96") (pintype "bidirectional"))
    )
    (net (code "120") (name "unconnected-(U101A-P0[4]{slash}I2SRX_CLK{slash}RD2{slash}CAP2[0]-Pad168)") (class "Default")
      (node (ref "U101") (pin "168") (pinfunction "P0[4]/I2SRX_CLK/RD2/CAP2[0]_168") (pintype "bidirectional"))
    )
    (net (code "121") (name "unconnected-(U101A-P0[5]{slash}I2SRX_WS{slash}TD2{slash}CAP2[1]-Pad166)") (class "Default")
      (node (ref "U101") (pin "166") (pinfunction "P0[5]/I2SRX_WS/TD2/CAP2[1]_166") (pintype "bidirectional"))
    )
    (net (code "122") (name "unconnected-(U101A-P0[6]{slash}I2SRX_SDA{slash}SSEL1{slash}MAT2[0]-Pad164)") (class "Default")
      (node (ref "U101") (pin "164") (pinfunction "P0[6]/I2SRX_SDA/SSEL1/MAT2[0]_164") (pintype "bidirectional"))
    )
    (net (code "123") (name "unconnected-(U101A-P0[7]{slash}I2STX_CLK{slash}SCK1{slash}MAT2[1]-Pad162)") (class "Default")
      (node (ref "U101") (pin "162") (pinfunction "P0[7]/I2STX_CLK/SCK1/MAT2[1]_162") (pintype "bidirectional"))
    )
    (net (code "124") (name "unconnected-(U101A-P0[8]{slash}I2STX_WS{slash}MISO1{slash}MAT2[2]-Pad160)") (class "Default")
      (node (ref "U101") (pin "160") (pinfunction "P0[8]/I2STX_WS/MISO1/MAT2[2]_160") (pintype "bidirectional"))
    )
    (net (code "125") (name "unconnected-(U101A-P0[9]{slash}I2STX_SDA{slash}MOSI1{slash}MAT2[3]-Pad158)") (class "Default")
      (node (ref "U101") (pin "158") (pinfunction "P0[9]/I2STX_SDA/MOSI1/MAT2[3]_158") (pintype "bidirectional"))
    )
    (net (code "126") (name "unconnected-(U101A-P0[10]{slash}TXD2{slash}SDA2{slash}MAT3[0]-Pad98)") (class "Default")
      (node (ref "U101") (pin "98") (pinfunction "P0[10]/TXD2/SDA2/MAT3[0]_98") (pintype "bidirectional"))
    )
    (net (code "127") (name "unconnected-(U101A-P0[11]{slash}RXD2{slash}SCL2{slash}MAT3[1]-Pad100)") (class "Default")
      (node (ref "U101") (pin "100") (pinfunction "P0[11]/RXD2/SCL2/MAT3[1]_100") (pintype "bidirectional"))
    )
    (net (code "128") (name "unconnected-(U101A-P0[12]{slash}~{USB_PPWR}2{slash}MISO1{slash}AD0[6]-Pad41)") (class "Default")
      (node (ref "U101") (pin "41") (pinfunction "P0[12]/~{USB_PPWR}2/MISO1/AD0[6]_41") (pintype "bidirectional"))
    )
    (net (code "129") (name "unconnected-(U101A-P0[13]{slash}USB_UP_LED2{slash}MOSI1{slash}AD0[7]-Pad45)") (class "Default")
      (node (ref "U101") (pin "45") (pinfunction "P0[13]/USB_UP_LED2/MOSI1/AD0[7]_45") (pintype "bidirectional"))
    )
    (net (code "130") (name "unconnected-(U101A-P0[15]{slash}TXD1{slash}SCK0{slash}SCK-Pad128)") (class "Default")
      (node (ref "U101") (pin "128") (pinfunction "P0[15]/TXD1/SCK0/SCK_128") (pintype "bidirectional"))
    )
    (net (code "131") (name "unconnected-(U101A-P0[16]{slash}RXD1{slash}SSEL0{slash}SSEL-Pad130)") (class "Default")
      (node (ref "U101") (pin "130") (pinfunction "P0[16]/RXD1/SSEL0/SSEL_130") (pintype "bidirectional"))
    )
    (net (code "132") (name "unconnected-(U101A-P0[17]{slash}CTS1{slash}MISO0{slash}MISO-Pad126)") (class "Default")
      (node (ref "U101") (pin "126") (pinfunction "P0[17]/CTS1/MISO0/MISO_126") (pintype "bidirectional"))
    )
    (net (code "133") (name "unconnected-(U101A-P0[18]{slash}DCD1{slash}MOSI0{slash}MOSI-Pad124)") (class "Default")
      (node (ref "U101") (pin "124") (pinfunction "P0[18]/DCD1/MOSI0/MOSI_124") (pintype "bidirectional"))
    )
    (net (code "134") (name "unconnected-(U101A-P0[19]{slash}DSR1{slash}MCICLK{slash}SDA1-Pad122)") (class "Default")
      (node (ref "U101") (pin "122") (pinfunction "P0[19]/DSR1/MCICLK/SDA1_122") (pintype "bidirectional"))
    )
    (net (code "135") (name "unconnected-(U101A-P0[20]{slash}DTR1{slash}MCICMD{slash}SCL1-Pad120)") (class "Default")
      (node (ref "U101") (pin "120") (pinfunction "P0[20]/DTR1/MCICMD/SCL1_120") (pintype "bidirectional"))
    )
    (net (code "136") (name "unconnected-(U101A-P0[21]{slash}RI1{slash}MCIPWR{slash}RD1-Pad118)") (class "Default")
      (node (ref "U101") (pin "118") (pinfunction "P0[21]/RI1/MCIPWR/RD1_118") (pintype "bidirectional"))
    )
    (net (code "137") (name "unconnected-(U101A-P0[22]{slash}RTS1{slash}MCIDAT0{slash}TD1-Pad116)") (class "Default")
      (node (ref "U101") (pin "116") (pinfunction "P0[22]/RTS1/MCIDAT0/TD1_116") (pintype "bidirectional"))
    )
    (net (code "138") (name "unconnected-(U101A-P0[23]{slash}AD0[0]{slash}I2SRX_CLK{slash}CAP3[0]-Pad18)") (class "Default")
      (node (ref "U101") (pin "18") (pinfunction "P0[23]/AD0[0]/I2SRX_CLK/CAP3[0]_18") (pintype "bidirectional"))
    )
    (net (code "139") (name "unconnected-(U101A-P0[24]{slash}AD0[1]{slash}I2SRX_WS{slash}CAP3[1]-Pad16)") (class "Default")
      (node (ref "U101") (pin "16") (pinfunction "P0[24]/AD0[1]/I2SRX_WS/CAP3[1]_16") (pintype "bidirectional"))
    )
    (net (code "140") (name "unconnected-(U101A-P0[25]{slash}AD0[2]{slash}I2SRX_SDA{slash}TXD3-Pad14)") (class "Default")
      (node (ref "U101") (pin "14") (pinfunction "P0[25]/AD0[2]/I2SRX_SDA/TXD3_14") (pintype "bidirectional"))
    )
    (net (code "141") (name "unconnected-(U101A-P0[26]{slash}AD0[3]{slash}AOUT{slash}RXD3-Pad12)") (class "Default")
      (node (ref "U101") (pin "12") (pinfunction "P0[26]/AD0[3]/AOUT/RXD3_12") (pintype "bidirectional"))
    )
    (net (code "142") (name "unconnected-(U101A-P0[27]{slash}SDA0-Pad50)") (class "Default")
      (node (ref "U101") (pin "50") (pinfunction "P0[27]/SDA0_50") (pintype "bidirectional"))
    )
    (net (code "143") (name "unconnected-(U101A-P0[28]{slash}SCL0-Pad48)") (class "Default")
      (node (ref "U101") (pin "48") (pinfunction "P0[28]/SCL0_48") (pintype "bidirectional"))
    )
    (net (code "144") (name "unconnected-(U101A-P0[29]{slash}USB_D+1-Pad61)") (class "Default")
      (node (ref "U101") (pin "61") (pinfunction "P0[29]/USB_D+1_61") (pintype "bidirectional"))
    )
    (net (code "145") (name "unconnected-(U101A-P0[30]{slash}USB_D-1-Pad62)") (class "Default")
      (node (ref "U101") (pin "62") (pinfunction "P0[30]/USB_D-1_62") (pintype "bidirectional"))
    )
    (net (code "146") (name "unconnected-(U101A-P0[31]{slash}USB_D+2-Pad51)") (class "Default")
      (node (ref "U101") (pin "51") (pinfunction "P0[31]/USB_D+2_51") (pintype "bidirectional"))
    )
    (net (code "147") (name "unconnected-(U101B-P1[0]{slash}ENET_TXD0-Pad196)") (class "Default")
      (node (ref "U101") (pin "196") (pinfunction "P1[0]/ENET_TXD0_196") (pintype "bidirectional"))
    )
    (net (code "148") (name "unconnected-(U101B-P1[1]{slash}ENET_TXD1-Pad194)") (class "Default")
      (node (ref "U101") (pin "194") (pinfunction "P1[1]/ENET_TXD1_194") (pintype "bidirectional"))
    )
    (net (code "149") (name "unconnected-(U101B-P1[2]{slash}ENET_TXD2{slash}MCICLK{slash}PWM0[1]-Pad185)") (class "Default")
      (node (ref "U101") (pin "185") (pinfunction "P1[2]/ENET_TXD2/MCICLK/PWM0[1]_185") (pintype "bidirectional"))
    )
    (net (code "150") (name "unconnected-(U101B-P1[3]{slash}ENET_TXD3{slash}MCICMD{slash}PWM0[2]-Pad177)") (class "Default")
      (node (ref "U101") (pin "177") (pinfunction "P1[3]/ENET_TXD3/MCICMD/PWM0[2]_177") (pintype "bidirectional"))
    )
    (net (code "151") (name "unconnected-(U101B-P1[4]{slash}ENET_TX_EN-Pad192)") (class "Default")
      (node (ref "U101") (pin "192") (pinfunction "P1[4]/ENET_TX_EN_192") (pintype "bidirectional"))
    )
    (net (code "152") (name "unconnected-(U101B-P1[5]{slash}ENET_TX_ER{slash}MCIPWR{slash}PWM0[3]-Pad156)") (class "Default")
      (node (ref "U101") (pin "156") (pinfunction "P1[5]/ENET_TX_ER/MCIPWR/PWM0[3]_156") (pintype "bidirectional"))
    )
    (net (code "153") (name "unconnected-(U101B-P1[6]{slash}ENET_TX_CLK{slash}MCIDAT0{slash}PWM0[4]-Pad171)") (class "Default")
      (node (ref "U101") (pin "171") (pinfunction "P1[6]/ENET_TX_CLK/MCIDAT0/PWM0[4]_171") (pintype "bidirectional"))
    )
    (net (code "154") (name "unconnected-(U101B-P1[7]{slash}ENET_COL{slash}MCIDAT1{slash}PWM0[5]-Pad153)") (class "Default")
      (node (ref "U101") (pin "153") (pinfunction "P1[7]/ENET_COL/MCIDAT1/PWM0[5]_153") (pintype "bidirectional"))
    )
    (net (code "155") (name "unconnected-(U101B-P1[8]{slash}ENET_CRS_DV{slash}ENET_CRS-Pad190)") (class "Default")
      (node (ref "U101") (pin "190") (pinfunction "P1[8]/ENET_CRS_DV/ENET_CRS_190") (pintype "bidirectional"))
    )
    (net (code "156") (name "unconnected-(U101B-P1[9]{slash}ENET_RXD0-Pad188)") (class "Default")
      (node (ref "U101") (pin "188") (pinfunction "P1[9]/ENET_RXD0_188") (pintype "bidirectional"))
    )
    (net (code "157") (name "unconnected-(U101B-P1[10]{slash}ENET_RXD1-Pad186)") (class "Default")
      (node (ref "U101") (pin "186") (pinfunction "P1[10]/ENET_RXD1_186") (pintype "bidirectional"))
    )
    (net (code "158") (name "unconnected-(U101B-P1[11]{slash}ENET_RXD2{slash}MCIDAT2{slash}PWM0[6]-Pad163)") (class "Default")
      (node (ref "U101") (pin "163") (pinfunction "P1[11]/ENET_RXD2/MCIDAT2/PWM0[6]_163") (pintype "bidirectional"))
    )
    (net (code "159") (name "unconnected-(U101B-P1[12]{slash}ENET_RXD3{slash}MCIDAT3{slash}PCAP0[0]-Pad157)") (class "Default")
      (node (ref "U101") (pin "157") (pinfunction "P1[12]/ENET_RXD3/MCIDAT3/PCAP0[0]_157") (pintype "bidirectional"))
    )
    (net (code "160") (name "unconnected-(U101B-P1[13]{slash}ENET_RX_DV-Pad147)") (class "Default")
      (node (ref "U101") (pin "147") (pinfunction "P1[13]/ENET_RX_DV_147") (pintype "bidirectional"))
    )
    (net (code "161") (name "unconnected-(U101B-P1[14]{slash}ENET_RX_ER-Pad184)") (class "Default")
      (node (ref "U101") (pin "184") (pinfunction "P1[14]/ENET_RX_ER_184") (pintype "bidirectional"))
    )
    (net (code "162") (name "unconnected-(U101B-P1[15]{slash}ENET_REF_CLK{slash}ENET_RX_CLK-Pad182)") (class "Default")
      (node (ref "U101") (pin "182") (pinfunction "P1[15]/ENET_REF_CLK/ENET_RX_CLK_182") (pintype "bidirectional"))
    )
    (net (code "163") (name "unconnected-(U101B-P1[16]{slash}ENET_MDC-Pad180)") (class "Default")
      (node (ref "U101") (pin "180") (pinfunction "P1[16]/ENET_MDC_180") (pintype "bidirectional"))
    )
    (net (code "164") (name "unconnected-(U101B-P1[17]{slash}ENET_MDIO-Pad178)") (class "Default")
      (node (ref "U101") (pin "178") (pinfunction "P1[17]/ENET_MDIO_178") (pintype "bidirectional"))
    )
    (net (code "165") (name "unconnected-(U101B-P1[27]{slash}~{USB_INT}1{slash}~{USB_OVRCR}1{slash}CAP0[1]-Pad88)") (class "Default")
      (node (ref "U101") (pin "88") (pinfunction "P1[27]/~{USB_INT}1/~{USB_OVRCR}1/CAP0[1]_88") (pintype "bidirectional"))
    )
    (net (code "166") (name "unconnected-(U101B-P1[28]{slash}USB_SCL1{slash}PCAP1[0]{slash}MAT0[0]-Pad90)") (class "Default")
      (node (ref "U101") (pin "90") (pinfunction "P1[28]/USB_SCL1/PCAP1[0]/MAT0[0]_90") (pintype "bidirectional"))
    )
    (net (code "167") (name "unconnected-(U101B-P1[29]{slash}USB_SDA1{slash}PCAP1[1]{slash}MAT0[1]-Pad92)") (class "Default")
      (node (ref "U101") (pin "92") (pinfunction "P1[29]/USB_SDA1/PCAP1[1]/MAT0[1]_92") (pintype "bidirectional"))
    )
    (net (code "168") (name "unconnected-(U101B-P1[30]{slash}USB_PWRD2{slash}VBUS{slash}AD0[4]-Pad42)") (class "Default")
      (node (ref "U101") (pin "42") (pinfunction "P1[30]/USB_PWRD2/VBUS/AD0[4]_42") (pintype "bidirectional"))
    )
    (net (code "169") (name "unconnected-(U101B-P1[31]{slash}~{USB_OVRCR}2{slash}SCK1{slash}AD0[5]-Pad40)") (class "Default")
      (node (ref "U101") (pin "40") (pinfunction "P1[31]/~{USB_OVRCR}2/SCK1/AD0[5]_40") (pintype "bidirectional"))
    )
    (net (code "170") (name "unconnected-(U101C-P2[0]{slash}PWM1[1]{slash}TXD1{slash}TRACECLK-Pad154)") (class "Default")
      (node (ref "U101") (pin "154") (pinfunction "P2[0]/PWM1[1]/TXD1/TRACECLK_154") (pintype "bidirectional"))
    )
    (net (code "171") (name "unconnected-(U101C-P2[5]{slash}PWM1[6]{slash}DTR1{slash}TRACEPKT0-Pad140)") (class "Default")
      (node (ref "U101") (pin "140") (pinfunction "P2[5]/PWM1[6]/DTR1/TRACEPKT0_140") (pintype "bidirectional"))
    )
    (net (code "172") (name "unconnected-(U101C-P2[14]{slash}~{CS}2{slash}CAP2[0]{slash}SDA1-Pad91)") (class "Default")
      (node (ref "U101") (pin "91") (pinfunction "P2[14]/~{CS}2/CAP2[0]/SDA1_91") (pintype "bidirectional"))
    )
    (net (code "173") (name "unconnected-(U101C-P2[16]{slash}~{CAS}-Pad87)") (class "Default")
      (node (ref "U101") (pin "87") (pinfunction "P2[16]/~{CAS}_87") (pintype "bidirectional"))
    )
    (net (code "174") (name "unconnected-(U101C-P2[22]{slash}~{DYCS}2{slash}CAP3[0]{slash}SCK0-Pad85)") (class "Default")
      (node (ref "U101") (pin "85") (pinfunction "P2[22]/~{DYCS}2/CAP3[0]/SCK0_85") (pintype "bidirectional"))
    )
    (net (code "175") (name "unconnected-(U101C-P2[24]{slash}CKEOUT0-Pad53)") (class "Default")
      (node (ref "U101") (pin "53") (pinfunction "P2[24]/CKEOUT0_53") (pintype "bidirectional"))
    )
    (net (code "176") (name "unconnected-(U101C-P2[27]{slash}CKEOUT3{slash}MAT3[1]{slash}MOSI0-Pad47)") (class "Default")
      (node (ref "U101") (pin "47") (pinfunction "P2[27]/CKEOUT3/MAT3[1]/MOSI0_47") (pintype "bidirectional"))
    )
    (net (code "177") (name "unconnected-(U101C-P2[28]{slash}DQMOUT0-Pad49)") (class "Default")
      (node (ref "U101") (pin "49") (pinfunction "P2[28]/DQMOUT0_49") (pintype "bidirectional"))
    )
    (net (code "178") (name "unconnected-(U101C-P2[29]{slash}DQMOUT1-Pad43)") (class "Default")
      (node (ref "U101") (pin "43") (pinfunction "P2[29]/DQMOUT1_43") (pintype "bidirectional"))
    )
    (net (code "179") (name "unconnected-(U101C-P2[30]{slash}DQMOUT2{slash}MAT3[2]{slash}SDA2-Pad31)") (class "Default")
      (node (ref "U101") (pin "31") (pinfunction "P2[30]/DQMOUT2/MAT3[2]/SDA2_31") (pintype "bidirectional"))
    )
    (net (code "180") (name "unconnected-(U101C-P2[31]{slash}DQMOUT3{slash}MAT3[3]{slash}SCL2-Pad39)") (class "Default")
      (node (ref "U101") (pin "39") (pinfunction "P2[31]/DQMOUT3/MAT3[3]/SCL2_39") (pintype "bidirectional"))
    )
    (net (code "181") (name "unconnected-(U101D-P3[16]{slash}D16{slash}PWM0[1]{slash}TXD1-Pad137)") (class "Default")
      (node (ref "U101") (pin "137") (pinfunction "P3[16]/D16/PWM0[1]/TXD1_137") (pintype "bidirectional"))
    )
    (net (code "182") (name "unconnected-(U101D-P3[17]{slash}D17{slash}PWM0[2]{slash}RXD1-Pad143)") (class "Default")
      (node (ref "U101") (pin "143") (pinfunction "P3[17]/D17/PWM0[2]/RXD1_143") (pintype "bidirectional"))
    )
    (net (code "183") (name "unconnected-(U101D-P3[18]{slash}D18{slash}PWM0[3]{slash}CTS1-Pad151)") (class "Default")
      (node (ref "U101") (pin "151") (pinfunction "P3[18]/D18/PWM0[3]/CTS1_151") (pintype "bidirectional"))
    )
    (net (code "184") (name "unconnected-(U101D-P3[19]{slash}D19{slash}PWM0[4]{slash}DCD1-Pad161)") (class "Default")
      (node (ref "U101") (pin "161") (pinfunction "P3[19]/D19/PWM0[4]/DCD1_161") (pintype "bidirectional"))
    )
    (net (code "185") (name "unconnected-(U101D-P3[20]{slash}D20{slash}PWM0[5]{slash}DSR1-Pad167)") (class "Default")
      (node (ref "U101") (pin "167") (pinfunction "P3[20]/D20/PWM0[5]/DSR1_167") (pintype "bidirectional"))
    )
    (net (code "186") (name "unconnected-(U101D-P3[21]{slash}D21{slash}PWM0[6]{slash}DTR1-Pad175)") (class "Default")
      (node (ref "U101") (pin "175") (pinfunction "P3[21]/D21/PWM0[6]/DTR1_175") (pintype "bidirectional"))
    )
    (net (code "187") (name "unconnected-(U101D-P3[22]{slash}D22{slash}PCAP0[0]{slash}RI1-Pad195)") (class "Default")
      (node (ref "U101") (pin "195") (pinfunction "P3[22]/D22/PCAP0[0]/RI1_195") (pintype "bidirectional"))
    )
    (net (code "188") (name "unconnected-(U101D-P3[27]{slash}D27{slash}CAP1[0]{slash}PWM1[4]-Pad203)") (class "Default")
      (node (ref "U101") (pin "203") (pinfunction "P3[27]/D27/CAP1[0]/PWM1[4]_203") (pintype "bidirectional"))
    )
    (net (code "189") (name "unconnected-(U101D-P3[28]{slash}D28{slash}CAP1[1]{slash}PWM1[5]-Pad5)") (class "Default")
      (node (ref "U101") (pin "5") (pinfunction "P3[28]/D28/CAP1[1]/PWM1[5]_5") (pintype "bidirectional"))
    )
    (net (code "190") (name "unconnected-(U101D-P3[29]{slash}D29{slash}MAT1[0]{slash}PWM1[6]-Pad11)") (class "Default")
      (node (ref "U101") (pin "11") (pinfunction "P3[29]/D29/MAT1[0]/PWM1[6]_11") (pintype "bidirectional"))
    )
    (net (code "191") (name "unconnected-(U101D-P3[30]{slash}D30{slash}MAT1[1]{slash}RTS1-Pad19)") (class "Default")
      (node (ref "U101") (pin "19") (pinfunction "P3[30]/D30/MAT1[1]/RTS1_19") (pintype "bidirectional"))
    )
    (net (code "192") (name "unconnected-(U101D-P3[31]{slash}D31{slash}MAT1[2]-Pad25)") (class "Default")
      (node (ref "U101") (pin "25") (pinfunction "P3[31]/D31/MAT1[2]_25") (pintype "bidirectional"))
    )
    (net (code "193") (name "unconnected-(U101E-P4[0]{slash}A0-Pad75)") (class "Default")
      (node (ref "U101") (pin "75") (pinfunction "P4[0]/A0_75") (pintype "bidirectional+no_connect"))
    )
    (net (code "194") (name "unconnected-(U101E-P4[28]{slash}BLS2{slash}MAT2[0]{slash}TXD3-Pad170)") (class "Default")
      (node (ref "U101") (pin "170") (pinfunction "P4[28]/BLS2/MAT2[0]/TXD3_170") (pintype "bidirectional"))
    )
    (net (code "195") (name "unconnected-(U101E-P4[29]{slash}BLS3{slash}MAT2[1]{slash}RXD3-Pad176)") (class "Default")
      (node (ref "U101") (pin "176") (pinfunction "P4[29]/BLS3/MAT2[1]/RXD3_176") (pintype "bidirectional"))
    )
    (net (code "196") (name "unconnected-(U101F-ALARM-Pad37)") (class "Default")
      (node (ref "U101") (pin "37") (pinfunction "ALARM_37") (pintype "output+no_connect"))
    )
    (net (code "197") (name "unconnected-(U101F-USB_D-2-Pad52)") (class "Default")
      (node (ref "U101") (pin "52") (pinfunction "USB_D-2_52") (pintype "bidirectional+no_connect"))
    )
    (net (code "198") (name "unconnected-(U101H-VBAT-Pad38)") (class "Default")
      (node (ref "U101") (pin "38") (pinfunction "VBAT_38") (pintype "power_in+no_connect"))
    )
    (net (code "199") (name "unconnected-(U101I-NC-Pad30)") (class "Default")
      (node (ref "U101") (pin "30") (pinfunction "NC_30") (pintype "passive+no_connect"))
    )
    (net (code "200") (name "unconnected-(U101I-NC-Pad117)") (class "Default")
      (node (ref "U101") (pin "117") (pinfunction "NC_117") (pintype "passive+no_connect"))
    )
    (net (code "201") (name "unconnected-(U101I-NC-Pad141)") (class "Default")
      (node (ref "U101") (pin "141") (pinfunction "NC_141") (pintype "passive+no_connect"))
    )
    (net (code "202") (name "unconnected-(U102-DNU-Pad13)") (class "Default")
      (node (ref "U102") (pin "13") (pinfunction "DNU_13") (pintype "passive+no_connect"))
    )
    (net (code "203") (name "unconnected-(U102-NC-Pad10)") (class "Default")
      (node (ref "U102") (pin "10") (pinfunction "NC_10") (pintype "passive+no_connect"))
    )
  )
)
